# Pin_Expander_595.net
KiCad netlist of a schematic drawn in Altium Designer
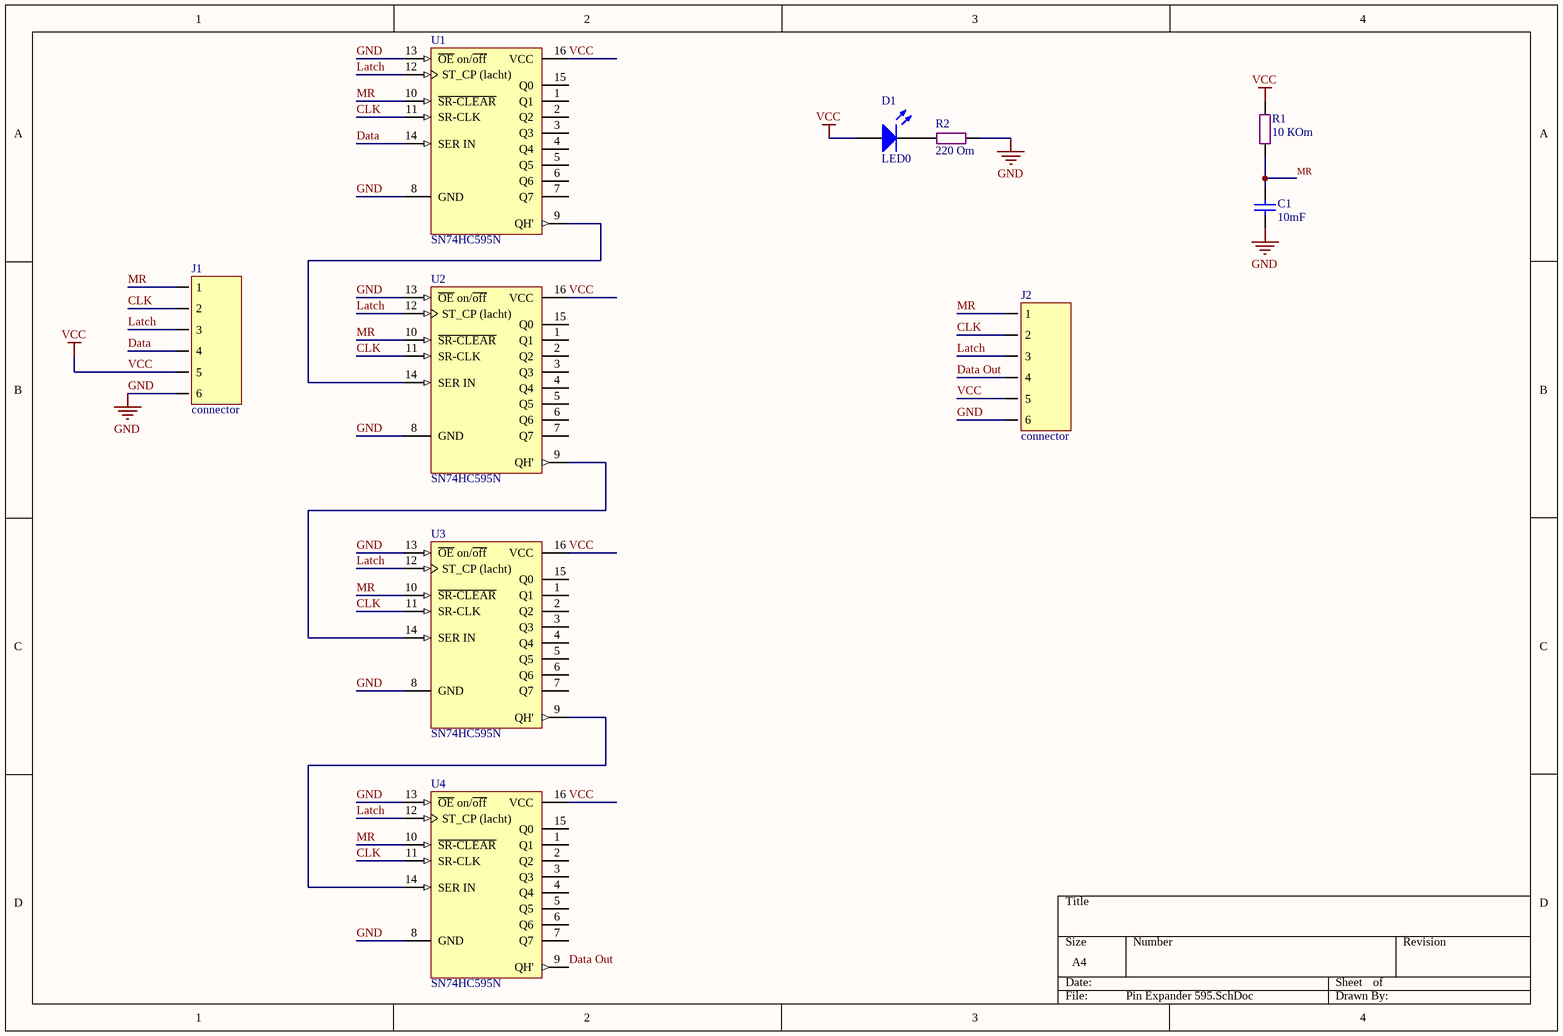
[diagram p0: Pin Expander 595.SchDoc]

(export (version "E")
  (design (tool "Eeschema 10.0.6"))
  (components
    (comp (ref "C1")
      (value "10mF")
      (footprint "bj Lib:Cap p2.54mm (2p)")
      (description "Capacitor")
      (libsource (lib "ss_ServersControl") (part "Cap"))
    )
    (comp (ref "D1")
      (value "LED0")
      (footprint "LED-0")
      (description "Typical INFRARED GaAs LED")
      (fields (field (name "PUBLISHER") "Altium Limited"))
      (libsource (lib "Miscellaneous Devices") (part "LED0"))
    )
    (comp (ref "J1")
      (value "connector")
      (footprint "bj Lib:Line 2.54 x 6")
      (description "6pin Connector")
      (libsource (lib "ss_ServersControl") (part "Connector ( 6 pin )"))
    )
    (comp (ref "J2")
      (value "connector")
      (footprint "bj Lib:Line 2.54 x 6")
      (description "6pin Connector")
      (libsource (lib "ss_ServersControl") (part "Connector ( 6 pin )"))
    )
    (comp (ref "R1")
      (value "10 КOm")
      (footprint "Res p7.62 (4p)")
      (libsource (lib "ss_ServersControl") (part "Resistor"))
    )
    (comp (ref "R2")
      (value "220 Om")
      (footprint "Res p7.62 (4p)")
      (libsource (lib "bj Lib") (part "Resistor"))
    )
    (comp (ref "U1")
      (value "SN74HC595N")
      (footprint "bj Lib:DIP16")
      (description "8-Bit Shift Register with 3-State Output Registers")
      (fields (field (name "PUBLISHER") "Altium Limited"))
      (libsource (lib "ss_ServersControl") (part "SN74HC595N"))
    )
    (comp (ref "U2")
      (value "SN74HC595N")
      (footprint "bj Lib:DIP16")
      (description "8-Bit Shift Register with 3-State Output Registers")
      (fields (field (name "PUBLISHER") "Altium Limited"))
      (libsource (lib "ss_ServersControl") (part "SN74HC595N"))
    )
    (comp (ref "U3")
      (value "SN74HC595N")
      (footprint "bj Lib:DIP16")
      (description "8-Bit Shift Register with 3-State Output Registers")
      (fields (field (name "PUBLISHER") "Altium Limited"))
      (libsource (lib "ss_ServersControl") (part "SN74HC595N"))
    )
    (comp (ref "U4")
      (value "SN74HC595N")
      (footprint "bj Lib:DIP16")
      (description "8-Bit Shift Register with 3-State Output Registers")
      (fields (field (name "PUBLISHER") "Altium Limited"))
      (libsource (lib "ss_ServersControl") (part "SN74HC595N"))
    )
  )
  (nets
    (net (code "1") (name "/CLK") (class "Default")
      (node (ref "J1") (pin "2") (pinfunction "2_2") (pintype "passive"))
      (node (ref "J2") (pin "2") (pinfunction "2_2") (pintype "passive"))
      (node (ref "U1") (pin "11") (pinfunction "SR-CLK_11") (pintype "input"))
      (node (ref "U2") (pin "11") (pinfunction "SR-CLK_11") (pintype "input"))
      (node (ref "U3") (pin "11") (pinfunction "SR-CLK_11") (pintype "input"))
      (node (ref "U4") (pin "11") (pinfunction "SR-CLK_11") (pintype "input"))
    )
    (net (code "2") (name "/Data") (class "Default")
      (node (ref "J1") (pin "4") (pinfunction "4_4") (pintype "passive"))
      (node (ref "U1") (pin "14") (pinfunction "SER_IN_14") (pintype "input"))
    )
    (net (code "3") (name "/Data Out") (class "Default")
      (node (ref "J2") (pin "4") (pinfunction "4_4") (pintype "passive"))
      (node (ref "U4") (pin "9") (pinfunction "QH'_9") (pintype "output"))
    )
    (net (code "4") (name "/Latch") (class "Default")
      (node (ref "J1") (pin "3") (pinfunction "3_3") (pintype "passive"))
      (node (ref "J2") (pin "3") (pinfunction "3_3") (pintype "passive"))
      (node (ref "U1") (pin "12") (pinfunction "ST_CP_(lacht)_12") (pintype "input"))
      (node (ref "U2") (pin "12") (pinfunction "ST_CP_(lacht)_12") (pintype "input"))
      (node (ref "U3") (pin "12") (pinfunction "ST_CP_(lacht)_12") (pintype "input"))
      (node (ref "U4") (pin "12") (pinfunction "ST_CP_(lacht)_12") (pintype "input"))
    )
    (net (code "5") (name "/MR") (class "Default")
      (node (ref "C1") (pin "2") (pinfunction "2_2") (pintype "passive"))
      (node (ref "J1") (pin "1") (pinfunction "1_1") (pintype "passive"))
      (node (ref "J2") (pin "1") (pinfunction "1_1") (pintype "passive"))
      (node (ref "R1") (pin "2") (pinfunction "2_2") (pintype "passive"))
      (node (ref "U1") (pin "10") (pinfunction "~{SR-CLEAR}_10") (pintype "input"))
      (node (ref "U2") (pin "10") (pinfunction "~{SR-CLEAR}_10") (pintype "input"))
      (node (ref "U3") (pin "10") (pinfunction "~{SR-CLEAR}_10") (pintype "input"))
      (node (ref "U4") (pin "10") (pinfunction "~{SR-CLEAR}_10") (pintype "input"))
    )
    (net (code "6") (name "GND") (class "Default")
      (node (ref "C1") (pin "1") (pinfunction "1_1") (pintype "passive"))
      (node (ref "J1") (pin "6") (pinfunction "6_6") (pintype "passive"))
      (node (ref "J2") (pin "6") (pinfunction "6_6") (pintype "passive"))
      (node (ref "R2") (pin "2") (pinfunction "2_2") (pintype "passive"))
      (node (ref "U1") (pin "13") (pinfunction "~{OE}_on/~{off}_13") (pintype "input"))
      (node (ref "U1") (pin "8") (pinfunction "GND_8") (pintype "power_in"))
      (node (ref "U2") (pin "13") (pinfunction "~{OE}_on/~{off}_13") (pintype "input"))
      (node (ref "U2") (pin "8") (pinfunction "GND_8") (pintype "power_in"))
      (node (ref "U3") (pin "13") (pinfunction "~{OE}_on/~{off}_13") (pintype "input"))
      (node (ref "U3") (pin "8") (pinfunction "GND_8") (pintype "power_in"))
      (node (ref "U4") (pin "13") (pinfunction "~{OE}_on/~{off}_13") (pintype "input"))
      (node (ref "U4") (pin "8") (pinfunction "GND_8") (pintype "power_in"))
    )
    (net (code "7") (name "Net-(D1-K)") (class "Default")
      (node (ref "D1") (pin "2") (pinfunction "K_2") (pintype "passive"))
      (node (ref "R2") (pin "1") (pinfunction "1_1") (pintype "passive"))
    )
    (net (code "8") (name "Net-(U1-QH')") (class "Default")
      (node (ref "U1") (pin "9") (pinfunction "QH'_9") (pintype "output"))
      (node (ref "U2") (pin "14") (pinfunction "SER_IN_14") (pintype "input"))
    )
    (net (code "9") (name "Net-(U2-QH')") (class "Default")
      (node (ref "U2") (pin "9") (pinfunction "QH'_9") (pintype "output"))
      (node (ref "U3") (pin "14") (pinfunction "SER_IN_14") (pintype "input"))
    )
    (net (code "10") (name "Net-(U3-QH')") (class "Default")
      (node (ref "U3") (pin "9") (pinfunction "QH'_9") (pintype "output"))
      (node (ref "U4") (pin "14") (pinfunction "SER_IN_14") (pintype "input"))
    )
    (net (code "11") (name "VCC") (class "Default")
      (node (ref "D1") (pin "1") (pinfunction "A_1") (pintype "passive"))
      (node (ref "J1") (pin "5") (pinfunction "5_5") (pintype "passive"))
      (node (ref "J2") (pin "5") (pinfunction "5_5") (pintype "passive"))
      (node (ref "R1") (pin "1") (pinfunction "1_1") (pintype "passive"))
      (node (ref "U1") (pin "16") (pinfunction "VCC_16") (pintype "power_in"))
      (node (ref "U2") (pin "16") (pinfunction "VCC_16") (pintype "power_in"))
      (node (ref "U3") (pin "16") (pinfunction "VCC_16") (pintype "power_in"))
      (node (ref "U4") (pin "16") (pinfunction "VCC_16") (pintype "power_in"))
    )
    (net (code "12") (name "unconnected-(U1-Q0-Pad15)") (class "Default")
      (node (ref "U1") (pin "15") (pinfunction "Q0_15") (pintype "tri_state"))
    )
    (net (code "13") (name "unconnected-(U1-Q1-Pad1)") (class "Default")
      (node (ref "U1") (pin "1") (pinfunction "Q1_1") (pintype "tri_state"))
    )
    (net (code "14") (name "unconnected-(U1-Q2-Pad2)") (class "Default")
      (node (ref "U1") (pin "2") (pinfunction "Q2_2") (pintype "tri_state"))
    )
    (net (code "15") (name "unconnected-(U1-Q3-Pad3)") (class "Default")
      (node (ref "U1") (pin "3") (pinfunction "Q3_3") (pintype "tri_state"))
    )
    (net (code "16") (name "unconnected-(U1-Q4-Pad4)") (class "Default")
      (node (ref "U1") (pin "4") (pinfunction "Q4_4") (pintype "tri_state"))
    )
    (net (code "17") (name "unconnected-(U1-Q5-Pad5)") (class "Default")
      (node (ref "U1") (pin "5") (pinfunction "Q5_5") (pintype "tri_state"))
    )
    (net (code "18") (name "unconnected-(U1-Q6-Pad6)") (class "Default")
      (node (ref "U1") (pin "6") (pinfunction "Q6_6") (pintype "tri_state"))
    )
    (net (code "19") (name "unconnected-(U1-Q7-Pad7)") (class "Default")
      (node (ref "U1") (pin "7") (pinfunction "Q7_7") (pintype "tri_state"))
    )
    (net (code "20") (name "unconnected-(U2-Q0-Pad15)") (class "Default")
      (node (ref "U2") (pin "15") (pinfunction "Q0_15") (pintype "tri_state"))
    )
    (net (code "21") (name "unconnected-(U2-Q1-Pad1)") (class "Default")
      (node (ref "U2") (pin "1") (pinfunction "Q1_1") (pintype "tri_state"))
    )
    (net (code "22") (name "unconnected-(U2-Q2-Pad2)") (class "Default")
      (node (ref "U2") (pin "2") (pinfunction "Q2_2") (pintype "tri_state"))
    )
    (net (code "23") (name "unconnected-(U2-Q3-Pad3)") (class "Default")
      (node (ref "U2") (pin "3") (pinfunction "Q3_3") (pintype "tri_state"))
    )
    (net (code "24") (name "unconnected-(U2-Q4-Pad4)") (class "Default")
      (node (ref "U2") (pin "4") (pinfunction "Q4_4") (pintype "tri_state"))
    )
    (net (code "25") (name "unconnected-(U2-Q5-Pad5)") (class "Default")
      (node (ref "U2") (pin "5") (pinfunction "Q5_5") (pintype "tri_state"))
    )
    (net (code "26") (name "unconnected-(U2-Q6-Pad6)") (class "Default")
      (node (ref "U2") (pin "6") (pinfunction "Q6_6") (pintype "tri_state"))
    )
    (net (code "27") (name "unconnected-(U2-Q7-Pad7)") (class "Default")
      (node (ref "U2") (pin "7") (pinfunction "Q7_7") (pintype "tri_state"))
    )
    (net (code "28") (name "unconnected-(U3-Q0-Pad15)") (class "Default")
      (node (ref "U3") (pin "15") (pinfunction "Q0_15") (pintype "tri_state"))
    )
    (net (code "29") (name "unconnected-(U3-Q1-Pad1)") (class "Default")
      (node (ref "U3") (pin "1") (pinfunction "Q1_1") (pintype "tri_state"))
    )
    (net (code "30") (name "unconnected-(U3-Q2-Pad2)") (class "Default")
      (node (ref "U3") (pin "2") (pinfunction "Q2_2") (pintype "tri_state"))
    )
    (net (code "31") (name "unconnected-(U3-Q3-Pad3)") (class "Default")
      (node (ref "U3") (pin "3") (pinfunction "Q3_3") (pintype "tri_state"))
    )
    (net (code "32") (name "unconnected-(U3-Q4-Pad4)") (class "Default")
      (node (ref "U3") (pin "4") (pinfunction "Q4_4") (pintype "tri_state"))
    )
    (net (code "33") (name "unconnected-(U3-Q5-Pad5)") (class "Default")
      (node (ref "U3") (pin "5") (pinfunction "Q5_5") (pintype "tri_state"))
    )
    (net (code "34") (name "unconnected-(U3-Q6-Pad6)") (class "Default")
      (node (ref "U3") (pin "6") (pinfunction "Q6_6") (pintype "tri_state"))
    )
    (net (code "35") (name "unconnected-(U3-Q7-Pad7)") (class "Default")
      (node (ref "U3") (pin "7") (pinfunction "Q7_7") (pintype "tri_state"))
    )
    (net (code "36") (name "unconnected-(U4-Q0-Pad15)") (class "Default")
      (node (ref "U4") (pin "15") (pinfunction "Q0_15") (pintype "tri_state"))
    )
    (net (code "37") (name "unconnected-(U4-Q1-Pad1)") (class "Default")
      (node (ref "U4") (pin "1") (pinfunction "Q1_1") (pintype "tri_state"))
    )
    (net (code "38") (name "unconnected-(U4-Q2-Pad2)") (class "Default")
      (node (ref "U4") (pin "2") (pinfunction "Q2_2") (pintype "tri_state"))
    )
    (net (code "39") (name "unconnected-(U4-Q3-Pad3)") (class "Default")
      (node (ref "U4") (pin "3") (pinfunction "Q3_3") (pintype "tri_state"))
    )
    (net (code "40") (name "unconnected-(U4-Q4-Pad4)") (class "Default")
      (node (ref "U4") (pin "4") (pinfunction "Q4_4") (pintype "tri_state"))
    )
    (net (code "41") (name "unconnected-(U4-Q5-Pad5)") (class "Default")
      (node (ref "U4") (pin "5") (pinfunction "Q5_5") (pintype "tri_state"))
    )
    (net (code "42") (name "unconnected-(U4-Q6-Pad6)") (class "Default")
      (node (ref "U4") (pin "6") (pinfunction "Q6_6") (pintype "tri_state"))
    )
    (net (code "43") (name "unconnected-(U4-Q7-Pad7)") (class "Default")
      (node (ref "U4") (pin "7") (pinfunction "Q7_7") (pintype "tri_state"))
    )
  )
)
